# Gain.net
KiCad netlist of a schematic drawn in Altium Designer
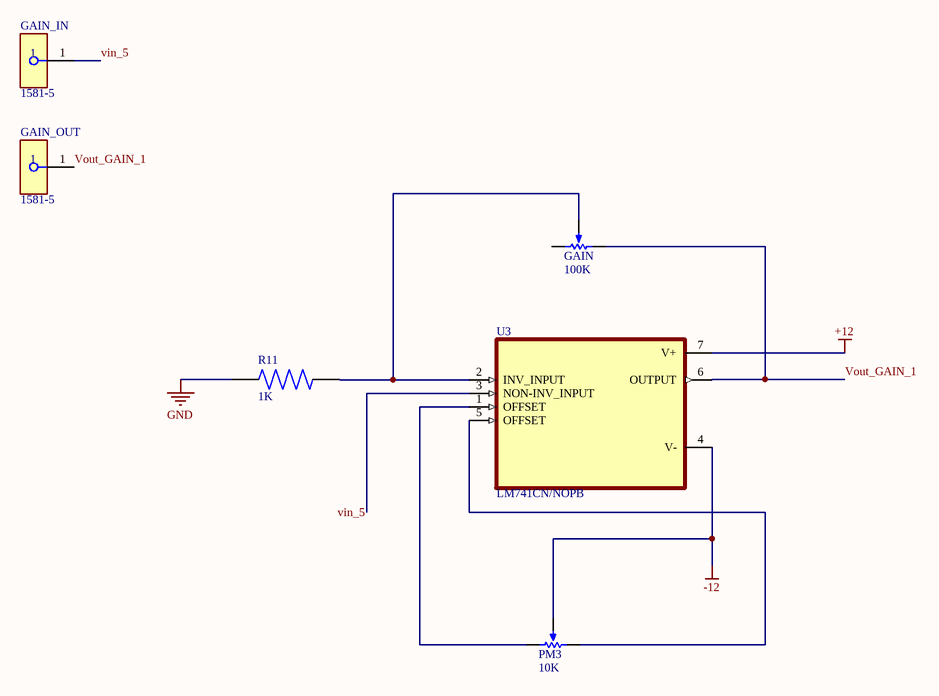
[diagram p0: Gain.SchDoc]

(export (version "E")
  (design (tool "Eeschema 10.0.6"))
  (components
    (comp (ref "GAIN")
      (value "100K")
      (footprint "PCBComponent_1")
      (libsource (lib "Integrated_Library1") (part "Component_1"))
    )
    (comp (ref "GAIN_IN")
      (value "1581-5")
      (footprint "FP-1581-5-MFG")
      (description "CONN BANANA JACK TURRET GREEN")
      (libsource (lib "Altium Content Vault") (part "c5c826e0c4b67fe3b42ef77f2d4decc"))
    )
    (comp (ref "GAIN_OUT")
      (value "1581-5")
      (footprint "FP-1581-5-MFG")
      (description "CONN BANANA JACK TURRET GREEN")
      (libsource (lib "Altium Content Vault") (part "c5c826e0c4b67fe3b42ef77f2d4decc"))
    )
    (comp (ref "PM3")
      (value "10K")
      (footprint "PCBComponent_1")
      (libsource (lib "Integrated_Library1") (part "Component_1"))
    )
    (comp (ref "R11")
      (value "1K")
      (footprint "RESAD1100W55L680D260")
      (description "1.07 kOhms Â±1% 0.25W, 1/4W Through Hole Resistor Axial - Metal Film")
      (fields (field (name "MF") "Yageo") (field (name "MP") "MFR-25FBF52-1K"))
      (libsource (lib "MFR-25FBF52-1K") (part "MFR-25FBF52-1K"))
    )
    (comp (ref "U3")
      (value "LM741CN/NOPB")
      (footprint "DIP794W45P254L959H508Q8")
      (description "Single, 44-V, 1-MHz operational amplifier")
      (fields (field (name "MF") "Texas Instruments"))
      (libsource (lib "LM741CN_NOPB (1)") (part "LM741CN/NOPB"))
    )
  )
  (nets
    (net (code "1") (name "+12") (class "Default")
      (node (ref "U3") (pin "7") (pinfunction "V+_7") (pintype "power_in"))
    )
    (net (code "2") (name "-12") (class "Default")
      (node (ref "PM3") (pin "2") (pinfunction "S_2") (pintype "passive"))
      (node (ref "U3") (pin "4") (pinfunction "V-_4") (pintype "power_in"))
    )
    (net (code "3") (name "/Vout_GAIN_1") (class "Default")
      (node (ref "GAIN") (pin "1") (pinfunction "CCW_1") (pintype "passive"))
      (node (ref "GAIN_OUT") (pin "1") (pinfunction "1_1") (pintype "passive"))
      (node (ref "U3") (pin "6") (pinfunction "OUTPUT_6") (pintype "output"))
    )
    (net (code "4") (name "/vin_5") (class "Default")
      (node (ref "GAIN_IN") (pin "1") (pinfunction "1_1") (pintype "passive"))
      (node (ref "U3") (pin "3") (pinfunction "NON-INV_INPUT_3") (pintype "input"))
    )
    (net (code "5") (name "GND") (class "Default")
      (node (ref "R11") (pin "1") (pinfunction "1_1") (pintype "passive"))
    )
    (net (code "6") (name "Net-(GAIN-S)") (class "Default")
      (node (ref "GAIN") (pin "2") (pinfunction "S_2") (pintype "passive"))
      (node (ref "R11") (pin "2") (pinfunction "2_2") (pintype "passive"))
      (node (ref "U3") (pin "2") (pinfunction "INV_INPUT_2") (pintype "input"))
    )
    (net (code "7") (name "Net-(PM3-CCW)") (class "Default")
      (node (ref "PM3") (pin "1") (pinfunction "CCW_1") (pintype "passive"))
      (node (ref "U3") (pin "5") (pinfunction "OFFSET_5") (pintype "input"))
    )
    (net (code "8") (name "Net-(PM3-CW)") (class "Default")
      (node (ref "PM3") (pin "3") (pinfunction "CW_3") (pintype "passive"))
      (node (ref "U3") (pin "1") (pinfunction "OFFSET_1") (pintype "input"))
    )
    (net (code "9") (name "unconnected-(GAIN-CW-Pad3)") (class "Default")
      (node (ref "GAIN") (pin "3") (pinfunction "CW_3") (pintype "passive"))
    )
  )
)
